# CH32V003_Programmer.net
KiCad netlist of a schematic drawn in EasyEDA Pro
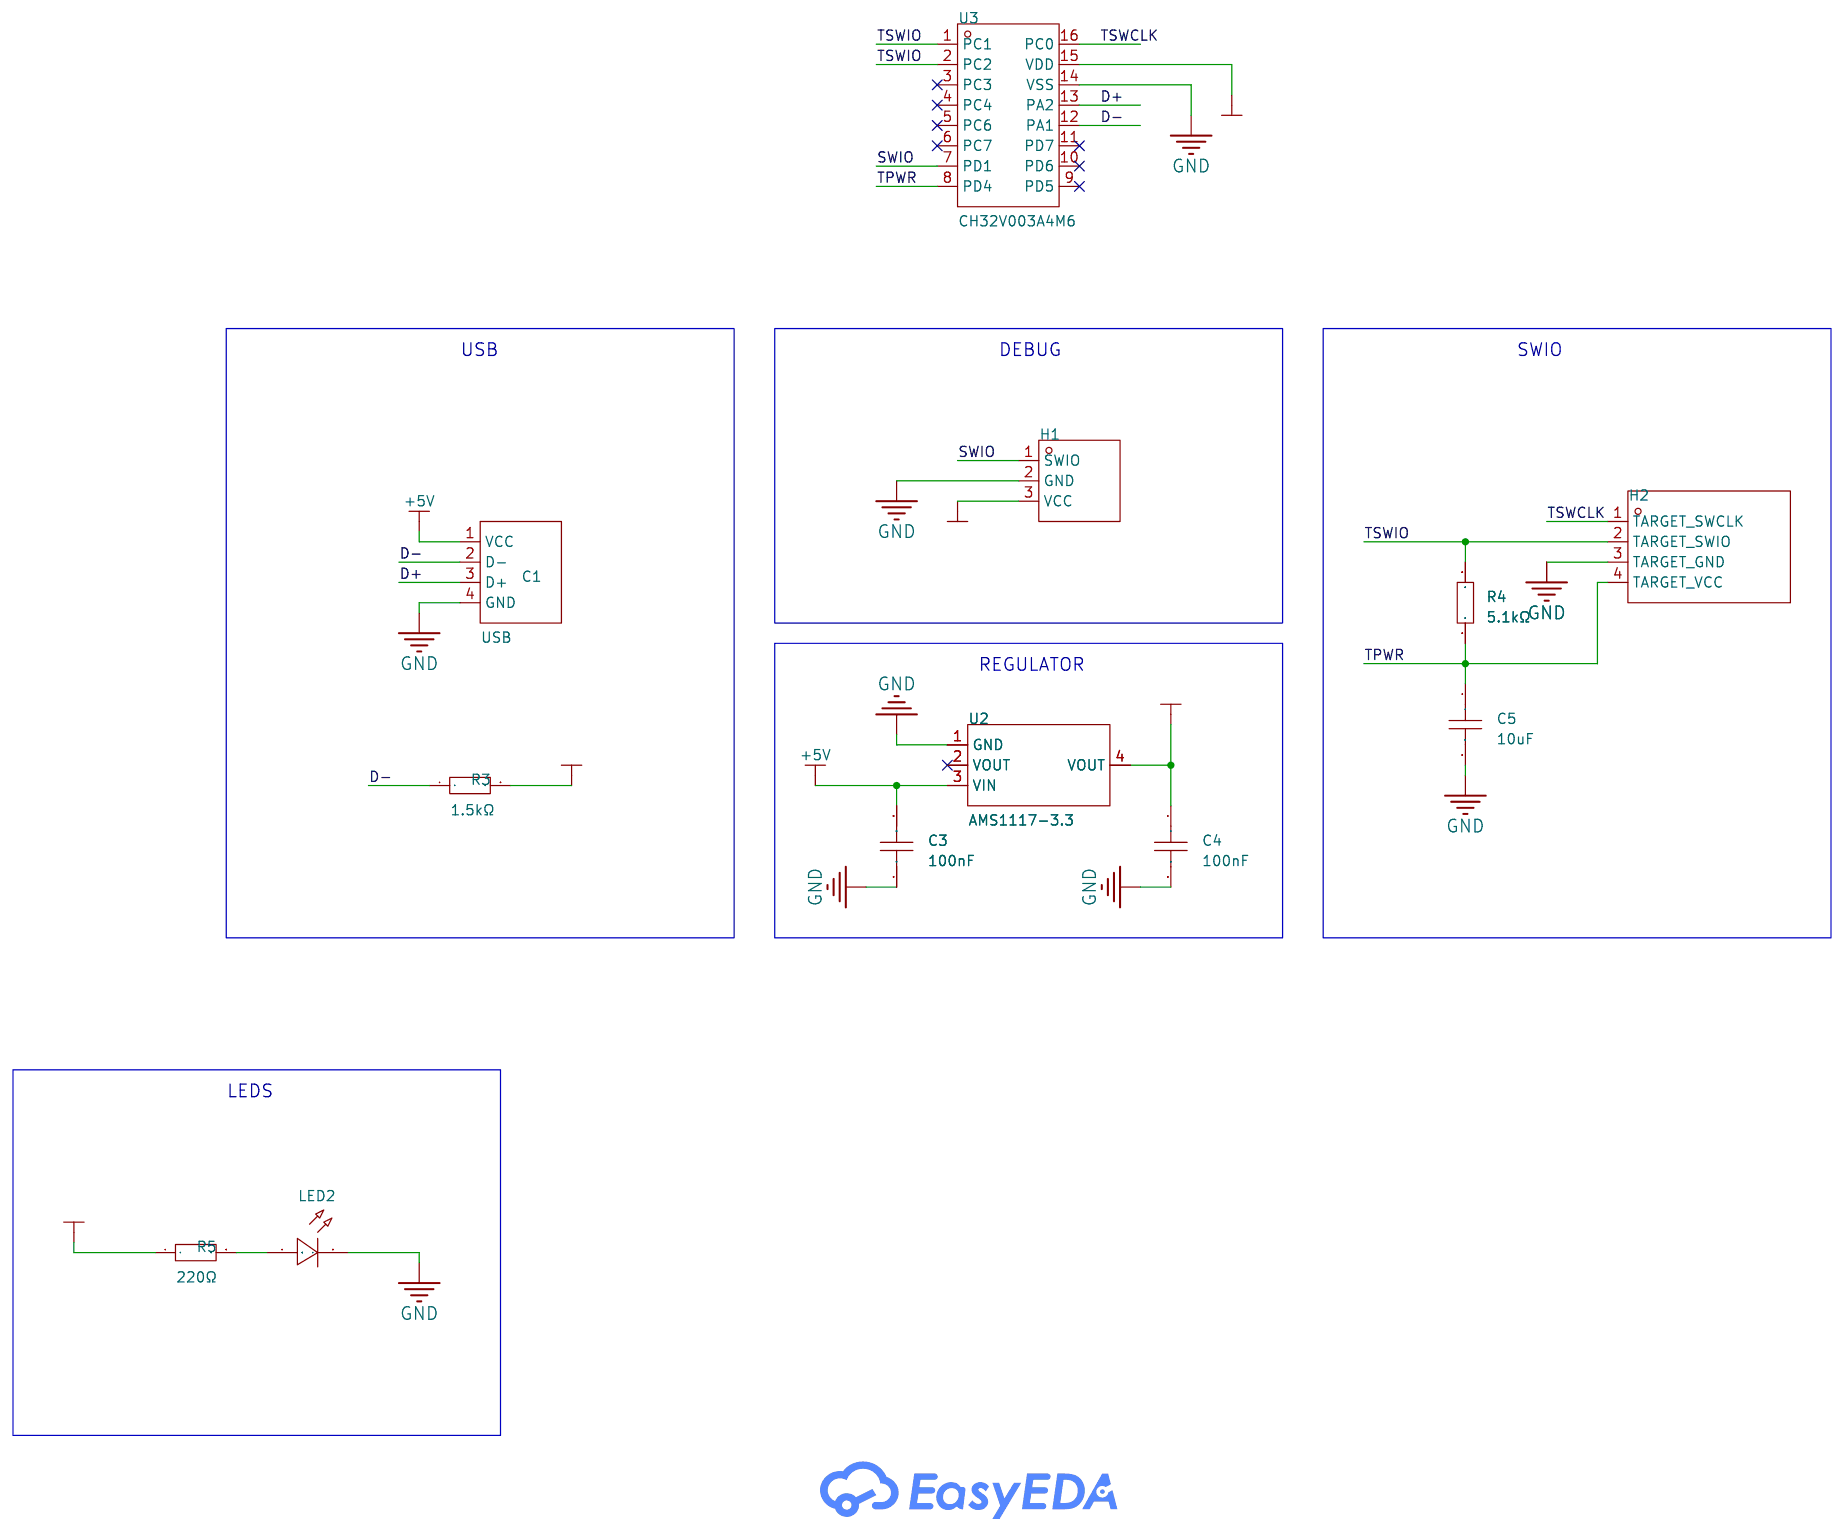
[diagram p0: schematic sheet]

(export (version "E")
  (design (tool "Eeschema 10.0.6"))
  (components
    (comp (ref "C1")
      (value "USB")
      (footprint "easyedapro:USB Type-C 4P")
      (libsource (lib "easyedapro") (part "USB Type-C 4P Board"))
    )
    (comp (ref "C3")
      (value "100nF")
      (footprint "easyedapro:CAP-TH_L5.8-W3.0-P4.7-D0.45")
      (fields (field (name "Manufacturer Part") "1C10Z5U104M050B") (field (name "Manufacturer") "VISHAY(威世)"))
      (libsource (lib "easyedapro") (part "1C10Z5U104M050B"))
    )
    (comp (ref "C4")
      (value "100nF")
      (footprint "easyedapro:CAP-TH_L5.8-W3.0-P4.7-D0.45")
      (fields (field (name "Manufacturer Part") "1C10Z5U104M050B") (field (name "Manufacturer") "VISHAY(威世)"))
      (libsource (lib "easyedapro") (part "1C10Z5U104M050B"))
    )
    (comp (ref "C5")
      (value "10uF")
      (footprint "easyedapro:CAP-TH_L5.8-W3.0-P4.7-D0.45")
      (fields (field (name "Manufacturer Part") "1C10Z5U104M050B") (field (name "Manufacturer") "VISHAY(威世)"))
      (libsource (lib "easyedapro") (part "1C10Z5U104M050B"))
    )
    (comp (ref "H1")
      (value "~")
      (footprint "easyedapro:HDR-TH_3P-P2.54-V-M")
      (libsource (lib "easyedapro") (part "PZ254V-11-03P_C2937625"))
    )
    (comp (ref "H2")
      (value "~")
      (footprint "easyedapro:HDR-TH_4P-P2.54-V-M")
      (libsource (lib "easyedapro") (part "PZ254V-11-04P"))
    )
    (comp (ref "LED2")
      (value "~")
      (footprint "easyedapro:LED-TH_BD3.0-P2.54-FD")
      (libsource (lib "easyedapro") (part "LED_TH-R"))
    )
    (comp (ref "R3")
      (value "1.5kΩ")
      (footprint "easyedapro:RES-TH_BD1.8-L3.2-P7.20-D0.4")
      (libsource (lib "easyedapro") (part "Res"))
    )
    (comp (ref "R4")
      (value "5.1kΩ")
      (footprint "easyedapro:RES-TH_BD1.8-L3.2-P7.20-D0.4")
      (libsource (lib "easyedapro") (part "Res"))
    )
    (comp (ref "R5")
      (value "220Ω")
      (footprint "easyedapro:RES-TH_BD1.8-L3.2-P7.20-D0.4")
      (libsource (lib "easyedapro") (part "Res"))
    )
    (comp (ref "U2")
      (value "AMS1117-3.3")
      (footprint "easyedapro:SOT-223-3_L6.5-W3.4-P2.30-LS7.0-BR")
      (fields (field (name "Manufacturer") "AMS"))
      (libsource (lib "easyedapro") (part "AMS1117-3.3"))
    )
    (comp (ref "U3")
      (value "CH32V003A4M6")
      (footprint "easyedapro:SOIC-16_L9.9-W3.9-P1.27-LS6.0-BL")
      (fields (field (name "Manufacturer") "WCH(南京沁恒)"))
      (libsource (lib "easyedapro") (part "CH32V003A4M6"))
    )
  )
  (nets
    (net (code "1") (name "+3.3V") (class "Default")
      (node (ref "C4") (pin "1") (pinfunction "1_1") (pintype "unspecified"))
      (node (ref "H1") (pin "3") (pinfunction "VCC_3") (pintype "unspecified"))
      (node (ref "R3") (pin "2") (pinfunction "2_2") (pintype "input"))
      (node (ref "R5") (pin "1") (pinfunction "1_1") (pintype "input"))
      (node (ref "U2") (pin "4") (pinfunction "VOUT_4") (pintype "unspecified"))
      (node (ref "U3") (pin "15") (pinfunction "VDD_15") (pintype "unspecified"))
    )
    (net (code "2") (name "+5V") (class "Default")
      (node (ref "C1") (pin "1") (pinfunction "VCC_1") (pintype "input"))
      (node (ref "C3") (pin "2") (pinfunction "2_2") (pintype "unspecified"))
      (node (ref "U2") (pin "3") (pinfunction "VIN_3") (pintype "unspecified"))
    )
    (net (code "3") (name "/D+") (class "Default")
      (node (ref "C1") (pin "3") (pinfunction "D+_3") (pintype "input"))
      (node (ref "U3") (pin "13") (pinfunction "PA2_13") (pintype "unspecified"))
    )
    (net (code "4") (name "/D-") (class "Default")
      (node (ref "C1") (pin "2") (pinfunction "D-_2") (pintype "input"))
      (node (ref "R3") (pin "1") (pinfunction "1_1") (pintype "input"))
      (node (ref "U3") (pin "12") (pinfunction "PA1_12") (pintype "unspecified"))
    )
    (net (code "5") (name "/SWIO") (class "Default")
      (node (ref "H1") (pin "1") (pinfunction "SWIO_1") (pintype "unspecified"))
      (node (ref "U3") (pin "7") (pinfunction "PD1_7") (pintype "unspecified"))
    )
    (net (code "6") (name "/TPWR") (class "Default")
      (node (ref "C5") (pin "1") (pinfunction "1_1") (pintype "unspecified"))
      (node (ref "H2") (pin "4") (pinfunction "TARGET_VCC_4") (pintype "unspecified"))
      (node (ref "R4") (pin "1") (pinfunction "1_1") (pintype "input"))
      (node (ref "U3") (pin "8") (pinfunction "PD4_8") (pintype "unspecified"))
    )
    (net (code "7") (name "/TSWCLK") (class "Default")
      (node (ref "H2") (pin "1") (pinfunction "TARGET_SWCLK_1") (pintype "unspecified"))
      (node (ref "U3") (pin "16") (pinfunction "PC0_16") (pintype "unspecified"))
    )
    (net (code "8") (name "/TSWIO") (class "Default")
      (node (ref "H2") (pin "2") (pinfunction "TARGET_SWIO_2") (pintype "unspecified"))
      (node (ref "R4") (pin "2") (pinfunction "2_2") (pintype "input"))
      (node (ref "U3") (pin "1") (pinfunction "PC1_1") (pintype "unspecified"))
      (node (ref "U3") (pin "2") (pinfunction "PC2_2") (pintype "unspecified"))
    )
    (net (code "9") (name "GND") (class "Default")
      (node (ref "C1") (pin "4") (pinfunction "GND_4") (pintype "input"))
      (node (ref "C3") (pin "1") (pinfunction "1_1") (pintype "unspecified"))
      (node (ref "C4") (pin "2") (pinfunction "2_2") (pintype "unspecified"))
      (node (ref "C5") (pin "2") (pinfunction "2_2") (pintype "unspecified"))
      (node (ref "H1") (pin "2") (pinfunction "GND_2") (pintype "unspecified"))
      (node (ref "H2") (pin "3") (pinfunction "TARGET_GND_3") (pintype "unspecified"))
      (node (ref "LED2") (pin "2") (pinfunction "A_2") (pintype "input"))
      (node (ref "U2") (pin "1") (pinfunction "GND_1") (pintype "unspecified"))
      (node (ref "U3") (pin "14") (pinfunction "VSS_14") (pintype "unspecified"))
    )
    (net (code "10") (name "Net-(LED2-C)") (class "Default")
      (node (ref "LED2") (pin "1") (pinfunction "C_1") (pintype "input"))
      (node (ref "R5") (pin "2") (pinfunction "2_2") (pintype "input"))
    )
    (net (code "11") (name "unconnected-(U2-VOUT-Pad2)") (class "Default")
      (node (ref "U2") (pin "2") (pinfunction "VOUT_2") (pintype "unspecified+no_connect"))
    )
    (net (code "12") (name "unconnected-(U3-PC3-Pad3)") (class "Default")
      (node (ref "U3") (pin "3") (pinfunction "PC3_3") (pintype "unspecified+no_connect"))
    )
    (net (code "13") (name "unconnected-(U3-PC4-Pad4)") (class "Default")
      (node (ref "U3") (pin "4") (pinfunction "PC4_4") (pintype "unspecified+no_connect"))
    )
    (net (code "14") (name "unconnected-(U3-PC6-Pad5)") (class "Default")
      (node (ref "U3") (pin "5") (pinfunction "PC6_5") (pintype "unspecified+no_connect"))
    )
    (net (code "15") (name "unconnected-(U3-PC7-Pad6)") (class "Default")
      (node (ref "U3") (pin "6") (pinfunction "PC7_6") (pintype "unspecified+no_connect"))
    )
    (net (code "16") (name "unconnected-(U3-PD5-Pad9)") (class "Default")
      (node (ref "U3") (pin "9") (pinfunction "PD5_9") (pintype "unspecified+no_connect"))
    )
    (net (code "17") (name "unconnected-(U3-PD6-Pad10)") (class "Default")
      (node (ref "U3") (pin "10") (pinfunction "PD6_10") (pintype "unspecified+no_connect"))
    )
    (net (code "18") (name "unconnected-(U3-PD7-Pad11)") (class "Default")
      (node (ref "U3") (pin "11") (pinfunction "PD7_11") (pintype "unspecified+no_connect"))
    )
  )
)
